# Sheet2.net
KiCad netlist of a schematic drawn in Altium Designer
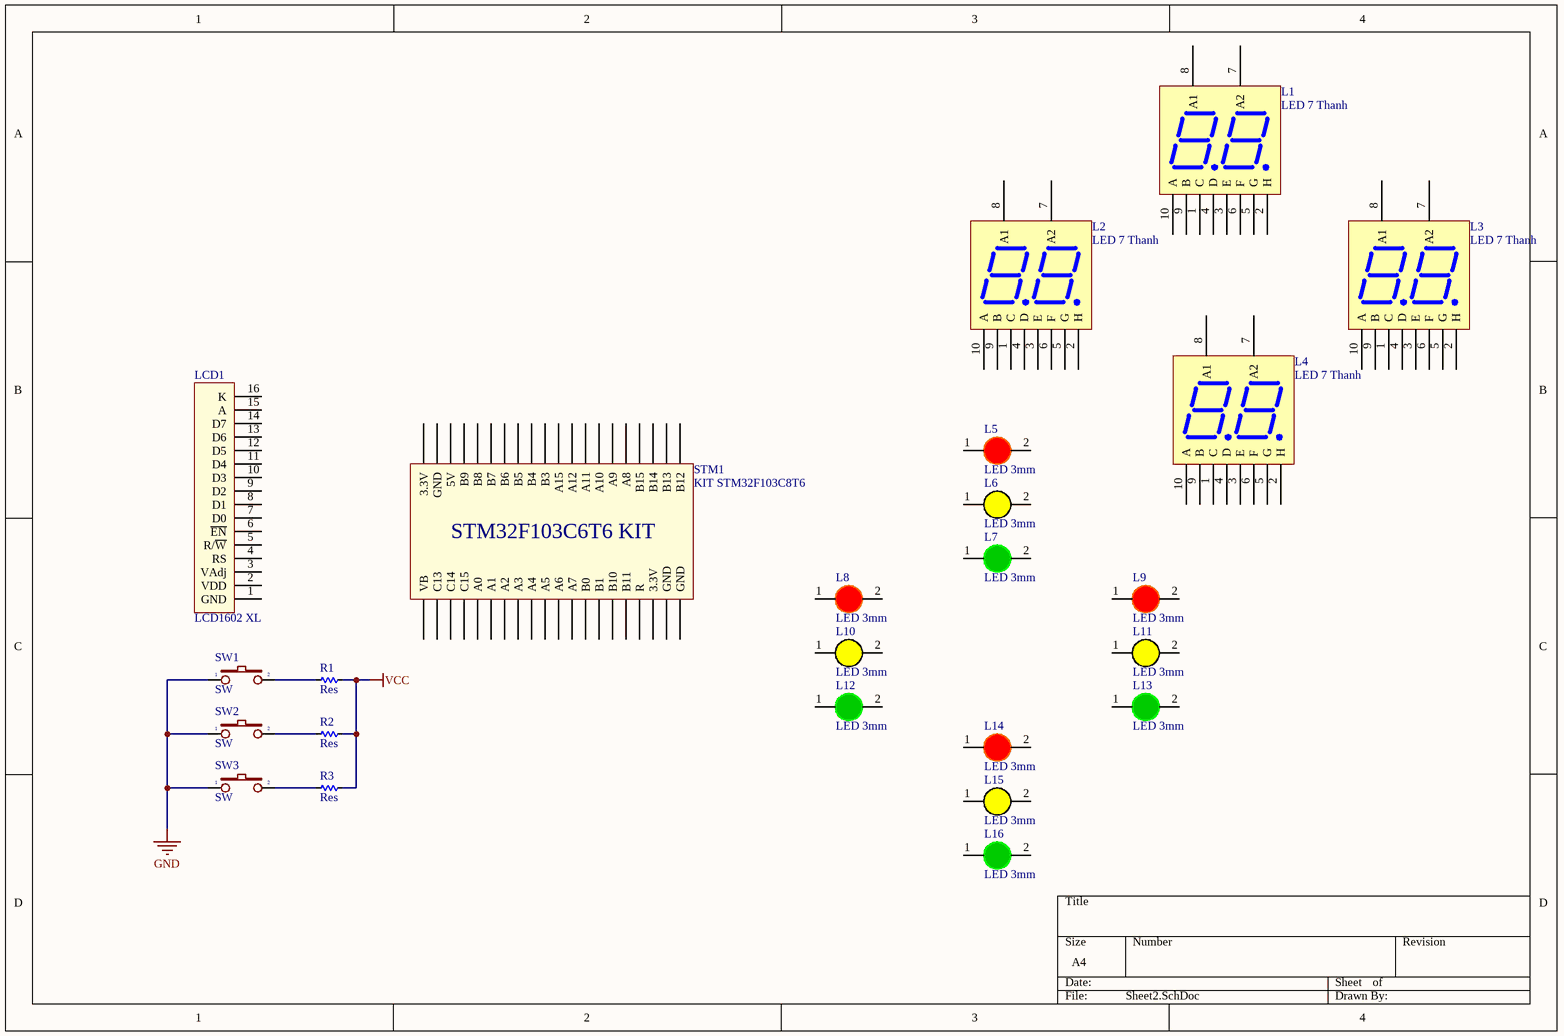
[diagram p0: Sheet2.SchDoc]

(export (version "E")
  (design (tool "Eeschema 10.0.6"))
  (components
    (comp (ref "L1")
      (value "LED 7 Thanh")
      (footprint "LED 7x2 0.56")
      (description "Dán")
      (libsource (lib "Altium_Lib_by_KhueNguyenCreator") (part "LED 7x2 0.56 Anot"))
    )
    (comp (ref "L2")
      (value "LED 7 Thanh")
      (footprint "LED 7x2 0.56")
      (description "Dán")
      (libsource (lib "Altium_Lib_by_KhueNguyenCreator") (part "LED 7x2 0.56 Anot"))
    )
    (comp (ref "L3")
      (value "LED 7 Thanh")
      (footprint "LED 7x2 0.56")
      (description "Dán")
      (libsource (lib "Altium_Lib_by_KhueNguyenCreator") (part "LED 7x2 0.56 Anot"))
    )
    (comp (ref "L4")
      (value "LED 7 Thanh")
      (footprint "LED 7x2 0.56")
      (description "Dán")
      (libsource (lib "Altium_Lib_by_KhueNguyenCreator") (part "LED 7x2 0.56 Anot"))
    )
    (comp (ref "L5")
      (value "LED 3mm")
      (footprint "LED-3MM-RED")
      (description "Cắm")
      (libsource (lib "Altium_Lib_by_KhueNguyenCreator") (part "LED 3mm Do"))
    )
    (comp (ref "L6")
      (value "LED 3mm")
      (footprint "LED-3MM-YELLOW")
      (description "Cắm")
      (libsource (lib "Altium_Lib_by_KhueNguyenCreator") (part "LED 3mm Vang"))
    )
    (comp (ref "L7")
      (value "LED 3mm")
      (footprint "LED-3MM-GREEN")
      (description "Cắm")
      (libsource (lib "Altium_Lib_by_KhueNguyenCreator") (part "LED 3mm Xanh La"))
    )
    (comp (ref "L8")
      (value "LED 3mm")
      (footprint "LED-3MM-RED")
      (description "Cắm")
      (libsource (lib "Altium_Lib_by_KhueNguyenCreator") (part "LED 3mm Do"))
    )
    (comp (ref "L9")
      (value "LED 3mm")
      (footprint "LED-3MM-RED")
      (description "Cắm")
      (libsource (lib "Altium_Lib_by_KhueNguyenCreator") (part "LED 3mm Do"))
    )
    (comp (ref "L10")
      (value "LED 3mm")
      (footprint "LED-3MM-YELLOW")
      (description "Cắm")
      (libsource (lib "Altium_Lib_by_KhueNguyenCreator") (part "LED 3mm Vang"))
    )
    (comp (ref "L11")
      (value "LED 3mm")
      (footprint "LED-3MM-YELLOW")
      (description "Cắm")
      (libsource (lib "Altium_Lib_by_KhueNguyenCreator") (part "LED 3mm Vang"))
    )
    (comp (ref "L12")
      (value "LED 3mm")
      (footprint "LED-3MM-GREEN")
      (description "Cắm")
      (libsource (lib "Altium_Lib_by_KhueNguyenCreator") (part "LED 3mm Xanh La"))
    )
    (comp (ref "L13")
      (value "LED 3mm")
      (footprint "LED-3MM-GREEN")
      (description "Cắm")
      (libsource (lib "Altium_Lib_by_KhueNguyenCreator") (part "LED 3mm Xanh La"))
    )
    (comp (ref "L14")
      (value "LED 3mm")
      (footprint "LED-3MM-RED")
      (description "Cắm")
      (libsource (lib "Altium_Lib_by_KhueNguyenCreator") (part "LED 3mm Do"))
    )
    (comp (ref "L15")
      (value "LED 3mm")
      (footprint "LED-3MM-YELLOW")
      (description "Cắm")
      (libsource (lib "Altium_Lib_by_KhueNguyenCreator") (part "LED 3mm Vang"))
    )
    (comp (ref "L16")
      (value "LED 3mm")
      (footprint "LED-3MM-GREEN")
      (description "Cắm")
      (libsource (lib "Altium_Lib_by_KhueNguyenCreator") (part "LED 3mm Xanh La"))
    )
    (comp (ref "LCD1")
      (value "LCD1602 XL")
      (footprint "LCD1602 with Jump")
      (description "LCD 1602 Xanh Lá")
      (libsource (lib "Altium_Lib_by_KhueNguyenCreator") (part "LCD1602 XL"))
    )
    (comp (ref "R1")
      (value "Res")
      (footprint "RES-1/2W")
      (fields
        (field (name "MANUFACTURER") "Generic Components")
        (field (name "PUBLISHER") "Altium Hobart Technology Centre")
      )
      (libsource (lib "thu vien 3d") (part "Res"))
    )
    (comp (ref "R2")
      (value "Res")
      (footprint "RES-1/2W")
      (fields
        (field (name "MANUFACTURER") "Generic Components")
        (field (name "PUBLISHER") "Altium Hobart Technology Centre")
      )
      (libsource (lib "thu vien 3d") (part "Res"))
    )
    (comp (ref "R3")
      (value "Res")
      (footprint "RES-1/2W")
      (fields
        (field (name "MANUFACTURER") "Generic Components")
        (field (name "PUBLISHER") "Altium Hobart Technology Centre")
      )
      (libsource (lib "thu vien 3d") (part "Res"))
    )
    (comp (ref "STM1")
      (value "KIT STM32F103C8T6")
      (footprint "STM32F103 KIT")
      (description "KIT STM32F103C8T6 Bluepill")
      (libsource (lib "Altium_Lib_by_KhueNguyenCreator") (part "STM32f103 Bluepill"))
    )
    (comp (ref "SW1")
      (value "SW")
      (footprint "SW1-SMD")
      (description "Switch button 2 pin")
      (libsource (lib "thu vien 3d") (part "SW2"))
    )
    (comp (ref "SW2")
      (value "SW")
      (footprint "SW1-SMD")
      (description "Switch button 2 pin")
      (libsource (lib "thu vien 3d") (part "SW2"))
    )
    (comp (ref "SW3")
      (value "SW")
      (footprint "SW1-SMD")
      (description "Switch button 2 pin")
      (libsource (lib "thu vien 3d") (part "SW2"))
    )
  )
  (nets
    (net (code "1") (name "GND") (class "Default")
      (node (ref "SW1") (pin "1") (pinfunction "1_1") (pintype "passive"))
      (node (ref "SW2") (pin "1") (pinfunction "1_1") (pintype "passive"))
      (node (ref "SW3") (pin "1") (pinfunction "1_1") (pintype "passive"))
    )
    (net (code "2") (name "Net-(R1-Pad2)") (class "Default")
      (node (ref "R1") (pin "2") (pinfunction "2_2") (pintype "passive"))
      (node (ref "SW1") (pin "2") (pinfunction "2_2") (pintype "passive"))
    )
    (net (code "3") (name "Net-(R2-Pad2)") (class "Default")
      (node (ref "R2") (pin "2") (pinfunction "2_2") (pintype "passive"))
      (node (ref "SW2") (pin "2") (pinfunction "2_2") (pintype "passive"))
    )
    (net (code "4") (name "Net-(R3-Pad2)") (class "Default")
      (node (ref "R3") (pin "2") (pinfunction "2_2") (pintype "passive"))
      (node (ref "SW3") (pin "2") (pinfunction "2_2") (pintype "passive"))
    )
    (net (code "5") (name "VCC") (class "Default")
      (node (ref "R1") (pin "1") (pinfunction "1_1") (pintype "passive"))
      (node (ref "R2") (pin "1") (pinfunction "1_1") (pintype "passive"))
      (node (ref "R3") (pin "1") (pinfunction "1_1") (pintype "passive"))
    )
    (net (code "6") (name "unconnected-(L1-A-Pad10)") (class "Default")
      (node (ref "L1") (pin "10") (pinfunction "A_10") (pintype "passive"))
    )
    (net (code "7") (name "unconnected-(L1-A1-Pad8)") (class "Default")
      (node (ref "L1") (pin "8") (pinfunction "A1_8") (pintype "passive"))
    )
    (net (code "8") (name "unconnected-(L1-A2-Pad7)") (class "Default")
      (node (ref "L1") (pin "7") (pinfunction "A2_7") (pintype "passive"))
    )
    (net (code "9") (name "unconnected-(L1-B-Pad9)") (class "Default")
      (node (ref "L1") (pin "9") (pinfunction "B_9") (pintype "passive"))
    )
    (net (code "10") (name "unconnected-(L1-C-Pad1)") (class "Default")
      (node (ref "L1") (pin "1") (pinfunction "C_1") (pintype "passive"))
    )
    (net (code "11") (name "unconnected-(L1-D-Pad4)") (class "Default")
      (node (ref "L1") (pin "4") (pinfunction "D_4") (pintype "passive"))
    )
    (net (code "12") (name "unconnected-(L1-E-Pad3)") (class "Default")
      (node (ref "L1") (pin "3") (pinfunction "E_3") (pintype "passive"))
    )
    (net (code "13") (name "unconnected-(L1-F-Pad6)") (class "Default")
      (node (ref "L1") (pin "6") (pinfunction "F_6") (pintype "passive"))
    )
    (net (code "14") (name "unconnected-(L1-G-Pad5)") (class "Default")
      (node (ref "L1") (pin "5") (pinfunction "G_5") (pintype "passive"))
    )
    (net (code "15") (name "unconnected-(L1-H-Pad2)") (class "Default")
      (node (ref "L1") (pin "2") (pinfunction "H_2") (pintype "passive"))
    )
    (net (code "16") (name "unconnected-(L2-A-Pad10)") (class "Default")
      (node (ref "L2") (pin "10") (pinfunction "A_10") (pintype "passive"))
    )
    (net (code "17") (name "unconnected-(L2-A1-Pad8)") (class "Default")
      (node (ref "L2") (pin "8") (pinfunction "A1_8") (pintype "passive"))
    )
    (net (code "18") (name "unconnected-(L2-A2-Pad7)") (class "Default")
      (node (ref "L2") (pin "7") (pinfunction "A2_7") (pintype "passive"))
    )
    (net (code "19") (name "unconnected-(L2-B-Pad9)") (class "Default")
      (node (ref "L2") (pin "9") (pinfunction "B_9") (pintype "passive"))
    )
    (net (code "20") (name "unconnected-(L2-C-Pad1)") (class "Default")
      (node (ref "L2") (pin "1") (pinfunction "C_1") (pintype "passive"))
    )
    (net (code "21") (name "unconnected-(L2-D-Pad4)") (class "Default")
      (node (ref "L2") (pin "4") (pinfunction "D_4") (pintype "passive"))
    )
    (net (code "22") (name "unconnected-(L2-E-Pad3)") (class "Default")
      (node (ref "L2") (pin "3") (pinfunction "E_3") (pintype "passive"))
    )
    (net (code "23") (name "unconnected-(L2-F-Pad6)") (class "Default")
      (node (ref "L2") (pin "6") (pinfunction "F_6") (pintype "passive"))
    )
    (net (code "24") (name "unconnected-(L2-G-Pad5)") (class "Default")
      (node (ref "L2") (pin "5") (pinfunction "G_5") (pintype "passive"))
    )
    (net (code "25") (name "unconnected-(L2-H-Pad2)") (class "Default")
      (node (ref "L2") (pin "2") (pinfunction "H_2") (pintype "passive"))
    )
    (net (code "26") (name "unconnected-(L3-A-Pad10)") (class "Default")
      (node (ref "L3") (pin "10") (pinfunction "A_10") (pintype "passive"))
    )
    (net (code "27") (name "unconnected-(L3-A1-Pad8)") (class "Default")
      (node (ref "L3") (pin "8") (pinfunction "A1_8") (pintype "passive"))
    )
    (net (code "28") (name "unconnected-(L3-A2-Pad7)") (class "Default")
      (node (ref "L3") (pin "7") (pinfunction "A2_7") (pintype "passive"))
    )
    (net (code "29") (name "unconnected-(L3-B-Pad9)") (class "Default")
      (node (ref "L3") (pin "9") (pinfunction "B_9") (pintype "passive"))
    )
    (net (code "30") (name "unconnected-(L3-C-Pad1)") (class "Default")
      (node (ref "L3") (pin "1") (pinfunction "C_1") (pintype "passive"))
    )
    (net (code "31") (name "unconnected-(L3-D-Pad4)") (class "Default")
      (node (ref "L3") (pin "4") (pinfunction "D_4") (pintype "passive"))
    )
    (net (code "32") (name "unconnected-(L3-E-Pad3)") (class "Default")
      (node (ref "L3") (pin "3") (pinfunction "E_3") (pintype "passive"))
    )
    (net (code "33") (name "unconnected-(L3-F-Pad6)") (class "Default")
      (node (ref "L3") (pin "6") (pinfunction "F_6") (pintype "passive"))
    )
    (net (code "34") (name "unconnected-(L3-G-Pad5)") (class "Default")
      (node (ref "L3") (pin "5") (pinfunction "G_5") (pintype "passive"))
    )
    (net (code "35") (name "unconnected-(L3-H-Pad2)") (class "Default")
      (node (ref "L3") (pin "2") (pinfunction "H_2") (pintype "passive"))
    )
    (net (code "36") (name "unconnected-(L4-A-Pad10)") (class "Default")
      (node (ref "L4") (pin "10") (pinfunction "A_10") (pintype "passive"))
    )
    (net (code "37") (name "unconnected-(L4-A1-Pad8)") (class "Default")
      (node (ref "L4") (pin "8") (pinfunction "A1_8") (pintype "passive"))
    )
    (net (code "38") (name "unconnected-(L4-A2-Pad7)") (class "Default")
      (node (ref "L4") (pin "7") (pinfunction "A2_7") (pintype "passive"))
    )
    (net (code "39") (name "unconnected-(L4-B-Pad9)") (class "Default")
      (node (ref "L4") (pin "9") (pinfunction "B_9") (pintype "passive"))
    )
    (net (code "40") (name "unconnected-(L4-C-Pad1)") (class "Default")
      (node (ref "L4") (pin "1") (pinfunction "C_1") (pintype "passive"))
    )
    (net (code "41") (name "unconnected-(L4-D-Pad4)") (class "Default")
      (node (ref "L4") (pin "4") (pinfunction "D_4") (pintype "passive"))
    )
    (net (code "42") (name "unconnected-(L4-E-Pad3)") (class "Default")
      (node (ref "L4") (pin "3") (pinfunction "E_3") (pintype "passive"))
    )
    (net (code "43") (name "unconnected-(L4-F-Pad6)") (class "Default")
      (node (ref "L4") (pin "6") (pinfunction "F_6") (pintype "passive"))
    )
    (net (code "44") (name "unconnected-(L4-G-Pad5)") (class "Default")
      (node (ref "L4") (pin "5") (pinfunction "G_5") (pintype "passive"))
    )
    (net (code "45") (name "unconnected-(L4-H-Pad2)") (class "Default")
      (node (ref "L4") (pin "2") (pinfunction "H_2") (pintype "passive"))
    )
    (net (code "46") (name "unconnected-(L5-A-Pad1)") (class "Default")
      (node (ref "L5") (pin "1") (pinfunction "A_1") (pintype "passive"))
    )
    (net (code "47") (name "unconnected-(L5-K-Pad2)") (class "Default")
      (node (ref "L5") (pin "2") (pinfunction "K_2") (pintype "passive"))
    )
    (net (code "48") (name "unconnected-(L6-A-Pad1)") (class "Default")
      (node (ref "L6") (pin "1") (pinfunction "A_1") (pintype "passive"))
    )
    (net (code "49") (name "unconnected-(L6-K-Pad2)") (class "Default")
      (node (ref "L6") (pin "2") (pinfunction "K_2") (pintype "passive"))
    )
    (net (code "50") (name "unconnected-(L7-A-Pad1)") (class "Default")
      (node (ref "L7") (pin "1") (pinfunction "A_1") (pintype "passive"))
    )
    (net (code "51") (name "unconnected-(L7-K-Pad2)") (class "Default")
      (node (ref "L7") (pin "2") (pinfunction "K_2") (pintype "passive"))
    )
    (net (code "52") (name "unconnected-(L8-A-Pad1)") (class "Default")
      (node (ref "L8") (pin "1") (pinfunction "A_1") (pintype "passive"))
    )
    (net (code "53") (name "unconnected-(L8-K-Pad2)") (class "Default")
      (node (ref "L8") (pin "2") (pinfunction "K_2") (pintype "passive"))
    )
    (net (code "54") (name "unconnected-(L9-A-Pad1)") (class "Default")
      (node (ref "L9") (pin "1") (pinfunction "A_1") (pintype "passive"))
    )
    (net (code "55") (name "unconnected-(L9-K-Pad2)") (class "Default")
      (node (ref "L9") (pin "2") (pinfunction "K_2") (pintype "passive"))
    )
    (net (code "56") (name "unconnected-(L10-A-Pad1)") (class "Default")
      (node (ref "L10") (pin "1") (pinfunction "A_1") (pintype "passive"))
    )
    (net (code "57") (name "unconnected-(L10-K-Pad2)") (class "Default")
      (node (ref "L10") (pin "2") (pinfunction "K_2") (pintype "passive"))
    )
    (net (code "58") (name "unconnected-(L11-A-Pad1)") (class "Default")
      (node (ref "L11") (pin "1") (pinfunction "A_1") (pintype "passive"))
    )
    (net (code "59") (name "unconnected-(L11-K-Pad2)") (class "Default")
      (node (ref "L11") (pin "2") (pinfunction "K_2") (pintype "passive"))
    )
    (net (code "60") (name "unconnected-(L12-A-Pad1)") (class "Default")
      (node (ref "L12") (pin "1") (pinfunction "A_1") (pintype "passive"))
    )
    (net (code "61") (name "unconnected-(L12-K-Pad2)") (class "Default")
      (node (ref "L12") (pin "2") (pinfunction "K_2") (pintype "passive"))
    )
    (net (code "62") (name "unconnected-(L13-A-Pad1)") (class "Default")
      (node (ref "L13") (pin "1") (pinfunction "A_1") (pintype "passive"))
    )
    (net (code "63") (name "unconnected-(L13-K-Pad2)") (class "Default")
      (node (ref "L13") (pin "2") (pinfunction "K_2") (pintype "passive"))
    )
    (net (code "64") (name "unconnected-(L14-A-Pad1)") (class "Default")
      (node (ref "L14") (pin "1") (pinfunction "A_1") (pintype "passive"))
    )
    (net (code "65") (name "unconnected-(L14-K-Pad2)") (class "Default")
      (node (ref "L14") (pin "2") (pinfunction "K_2") (pintype "passive"))
    )
    (net (code "66") (name "unconnected-(L15-A-Pad1)") (class "Default")
      (node (ref "L15") (pin "1") (pinfunction "A_1") (pintype "passive"))
    )
    (net (code "67") (name "unconnected-(L15-K-Pad2)") (class "Default")
      (node (ref "L15") (pin "2") (pinfunction "K_2") (pintype "passive"))
    )
    (net (code "68") (name "unconnected-(L16-A-Pad1)") (class "Default")
      (node (ref "L16") (pin "1") (pinfunction "A_1") (pintype "passive"))
    )
    (net (code "69") (name "unconnected-(L16-K-Pad2)") (class "Default")
      (node (ref "L16") (pin "2") (pinfunction "K_2") (pintype "passive"))
    )
    (net (code "70") (name "unconnected-(LCD1-A-Pad15)") (class "Default")
      (node (ref "LCD1") (pin "15") (pinfunction "A_15") (pintype "passive"))
    )
    (net (code "71") (name "unconnected-(LCD1-D0-Pad7)") (class "Default")
      (node (ref "LCD1") (pin "7") (pinfunction "D0_7") (pintype "passive"))
    )
    (net (code "72") (name "unconnected-(LCD1-D1-Pad8)") (class "Default")
      (node (ref "LCD1") (pin "8") (pinfunction "D1_8") (pintype "passive"))
    )
    (net (code "73") (name "unconnected-(LCD1-D2-Pad9)") (class "Default")
      (node (ref "LCD1") (pin "9") (pinfunction "D2_9") (pintype "passive"))
    )
    (net (code "74") (name "unconnected-(LCD1-D3-Pad10)") (class "Default")
      (node (ref "LCD1") (pin "10") (pinfunction "D3_10") (pintype "passive"))
    )
    (net (code "75") (name "unconnected-(LCD1-D4-Pad11)") (class "Default")
      (node (ref "LCD1") (pin "11") (pinfunction "D4_11") (pintype "passive"))
    )
    (net (code "76") (name "unconnected-(LCD1-D5-Pad12)") (class "Default")
      (node (ref "LCD1") (pin "12") (pinfunction "D5_12") (pintype "passive"))
    )
    (net (code "77") (name "unconnected-(LCD1-D6-Pad13)") (class "Default")
      (node (ref "LCD1") (pin "13") (pinfunction "D6_13") (pintype "passive"))
    )
    (net (code "78") (name "unconnected-(LCD1-D7-Pad14)") (class "Default")
      (node (ref "LCD1") (pin "14") (pinfunction "D7_14") (pintype "passive"))
    )
    (net (code "79") (name "unconnected-(LCD1-GND-Pad1)") (class "Default")
      (node (ref "LCD1") (pin "1") (pinfunction "GND_1") (pintype "passive"))
    )
    (net (code "80") (name "unconnected-(LCD1-K-Pad16)") (class "Default")
      (node (ref "LCD1") (pin "16") (pinfunction "K_16") (pintype "passive"))
    )
    (net (code "81") (name "unconnected-(LCD1-RS-Pad4)") (class "Default")
      (node (ref "LCD1") (pin "4") (pinfunction "RS_4") (pintype "passive"))
    )
    (net (code "82") (name "unconnected-(LCD1-R{slash}~{W}-Pad5)") (class "Default")
      (node (ref "LCD1") (pin "5") (pinfunction "R/~{W}_5") (pintype "passive"))
    )
    (net (code "83") (name "unconnected-(LCD1-VAdj-Pad3)") (class "Default")
      (node (ref "LCD1") (pin "3") (pinfunction "VAdj_3") (pintype "passive"))
    )
    (net (code "84") (name "unconnected-(LCD1-VDD-Pad2)") (class "Default")
      (node (ref "LCD1") (pin "2") (pinfunction "VDD_2") (pintype "passive"))
    )
    (net (code "85") (name "unconnected-(LCD1-~{EN}-Pad6)") (class "Default")
      (node (ref "LCD1") (pin "6") (pinfunction "~{EN}_6") (pintype "passive"))
    )
    (net (code "86") (name "unconnected-(STM1-3.3V-Pad20)") (class "Default")
      (node (ref "STM1") (pin "20") (pinfunction "3.3V_20") (pintype "passive"))
    )
    (net (code "87") (name "unconnected-(STM1-3.3V-Pad38)") (class "Default")
      (node (ref "STM1") (pin "38") (pinfunction "3.3V_38") (pintype "passive"))
    )
    (net (code "88") (name "unconnected-(STM1-5V-Pad18)") (class "Default")
      (node (ref "STM1") (pin "18") (pinfunction "5V_18") (pintype "passive"))
    )
    (net (code "89") (name "unconnected-(STM1-A0-Pad25)") (class "Default")
      (node (ref "STM1") (pin "25") (pinfunction "A0_25") (pintype "passive"))
    )
    (net (code "90") (name "unconnected-(STM1-A1-Pad26)") (class "Default")
      (node (ref "STM1") (pin "26") (pinfunction "A1_26") (pintype "passive"))
    )
    (net (code "91") (name "unconnected-(STM1-A2-Pad27)") (class "Default")
      (node (ref "STM1") (pin "27") (pinfunction "A2_27") (pintype "passive"))
    )
    (net (code "92") (name "unconnected-(STM1-A3-Pad28)") (class "Default")
      (node (ref "STM1") (pin "28") (pinfunction "A3_28") (pintype "passive"))
    )
    (net (code "93") (name "unconnected-(STM1-A4-Pad29)") (class "Default")
      (node (ref "STM1") (pin "29") (pinfunction "A4_29") (pintype "passive"))
    )
    (net (code "94") (name "unconnected-(STM1-A5-Pad30)") (class "Default")
      (node (ref "STM1") (pin "30") (pinfunction "A5_30") (pintype "passive"))
    )
    (net (code "95") (name "unconnected-(STM1-A6-Pad31)") (class "Default")
      (node (ref "STM1") (pin "31") (pinfunction "A6_31") (pintype "passive"))
    )
    (net (code "96") (name "unconnected-(STM1-A7-Pad32)") (class "Default")
      (node (ref "STM1") (pin "32") (pinfunction "A7_32") (pintype "passive"))
    )
    (net (code "97") (name "unconnected-(STM1-A8-Pad5)") (class "Default")
      (node (ref "STM1") (pin "5") (pinfunction "A8_5") (pintype "passive"))
    )
    (net (code "98") (name "unconnected-(STM1-A9-Pad6)") (class "Default")
      (node (ref "STM1") (pin "6") (pinfunction "A9_6") (pintype "passive"))
    )
    (net (code "99") (name "unconnected-(STM1-A10-Pad7)") (class "Default")
      (node (ref "STM1") (pin "7") (pinfunction "A10_7") (pintype "passive"))
    )
    (net (code "100") (name "unconnected-(STM1-A11-Pad8)") (class "Default")
      (node (ref "STM1") (pin "8") (pinfunction "A11_8") (pintype "passive"))
    )
    (net (code "101") (name "unconnected-(STM1-A12-Pad9)") (class "Default")
      (node (ref "STM1") (pin "9") (pinfunction "A12_9") (pintype "passive"))
    )
    (net (code "102") (name "unconnected-(STM1-A15-Pad10)") (class "Default")
      (node (ref "STM1") (pin "10") (pinfunction "A15_10") (pintype "passive"))
    )
    (net (code "103") (name "unconnected-(STM1-B0-Pad33)") (class "Default")
      (node (ref "STM1") (pin "33") (pinfunction "B0_33") (pintype "passive"))
    )
    (net (code "104") (name "unconnected-(STM1-B1-Pad34)") (class "Default")
      (node (ref "STM1") (pin "34") (pinfunction "B1_34") (pintype "passive"))
    )
    (net (code "105") (name "unconnected-(STM1-B3-Pad11)") (class "Default")
      (node (ref "STM1") (pin "11") (pinfunction "B3_11") (pintype "passive"))
    )
    (net (code "106") (name "unconnected-(STM1-B4-Pad12)") (class "Default")
      (node (ref "STM1") (pin "12") (pinfunction "B4_12") (pintype "passive"))
    )
    (net (code "107") (name "unconnected-(STM1-B5-Pad13)") (class "Default")
      (node (ref "STM1") (pin "13") (pinfunction "B5_13") (pintype "passive"))
    )
    (net (code "108") (name "unconnected-(STM1-B6-Pad14)") (class "Default")
      (node (ref "STM1") (pin "14") (pinfunction "B6_14") (pintype "passive"))
    )
    (net (code "109") (name "unconnected-(STM1-B7-Pad15)") (class "Default")
      (node (ref "STM1") (pin "15") (pinfunction "B7_15") (pintype "passive"))
    )
    (net (code "110") (name "unconnected-(STM1-B8-Pad16)") (class "Default")
      (node (ref "STM1") (pin "16") (pinfunction "B8_16") (pintype "passive"))
    )
    (net (code "111") (name "unconnected-(STM1-B9-Pad17)") (class "Default")
      (node (ref "STM1") (pin "17") (pinfunction "B9_17") (pintype "passive"))
    )
    (net (code "112") (name "unconnected-(STM1-B10-Pad35)") (class "Default")
      (node (ref "STM1") (pin "35") (pinfunction "B10_35") (pintype "passive"))
    )
    (net (code "113") (name "unconnected-(STM1-B11-Pad36)") (class "Default")
      (node (ref "STM1") (pin "36") (pinfunction "B11_36") (pintype "passive"))
    )
    (net (code "114") (name "unconnected-(STM1-B12-Pad1)") (class "Default")
      (node (ref "STM1") (pin "1") (pinfunction "B12_1") (pintype "passive"))
    )
    (net (code "115") (name "unconnected-(STM1-B13-Pad2)") (class "Default")
      (node (ref "STM1") (pin "2") (pinfunction "B13_2") (pintype "passive"))
    )
    (net (code "116") (name "unconnected-(STM1-B14-Pad3)") (class "Default")
      (node (ref "STM1") (pin "3") (pinfunction "B14_3") (pintype "passive"))
    )
    (net (code "117") (name "unconnected-(STM1-B15-Pad4)") (class "Default")
      (node (ref "STM1") (pin "4") (pinfunction "B15_4") (pintype "passive"))
    )
    (net (code "118") (name "unconnected-(STM1-C13-Pad22)") (class "Default")
      (node (ref "STM1") (pin "22") (pinfunction "C13_22") (pintype "passive"))
    )
    (net (code "119") (name "unconnected-(STM1-C14-Pad23)") (class "Default")
      (node (ref "STM1") (pin "23") (pinfunction "C14_23") (pintype "passive"))
    )
    (net (code "120") (name "unconnected-(STM1-C15-Pad24)") (class "Default")
      (node (ref "STM1") (pin "24") (pinfunction "C15_24") (pintype "passive"))
    )
    (net (code "121") (name "unconnected-(STM1-GND-Pad19)") (class "Default")
      (node (ref "STM1") (pin "19") (pinfunction "GND_19") (pintype "passive"))
    )
    (net (code "122") (name "unconnected-(STM1-GND-Pad39)") (class "Default")
      (node (ref "STM1") (pin "39") (pinfunction "GND_39") (pintype "passive"))
    )
    (net (code "123") (name "unconnected-(STM1-GND-Pad40)") (class "Default")
      (node (ref "STM1") (pin "40") (pinfunction "GND_40") (pintype "passive"))
    )
    (net (code "124") (name "unconnected-(STM1-R-Pad37)") (class "Default")
      (node (ref "STM1") (pin "37") (pinfunction "R_37") (pintype "passive"))
    )
    (net (code "125") (name "unconnected-(STM1-VB-Pad21)") (class "Default")
      (node (ref "STM1") (pin "21") (pinfunction "VB_21") (pintype "passive"))
    )
  )
)
